# NEW_MINI.net
KiCad netlist of a schematic drawn in Altium Designer
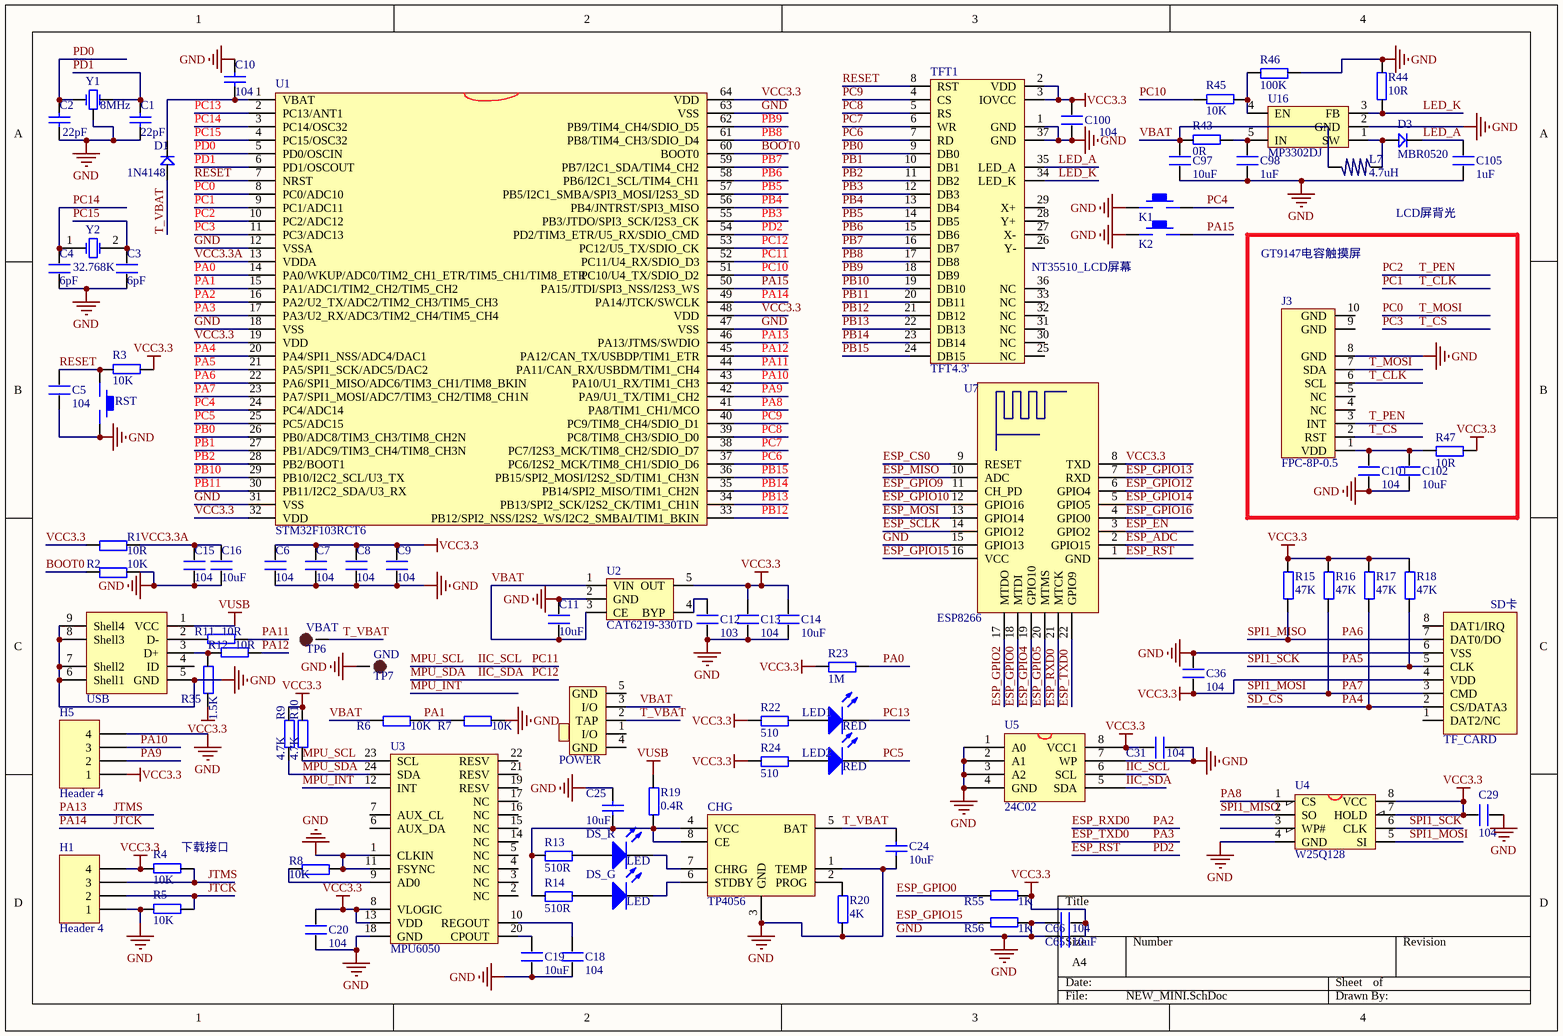
[diagram p0: NEW_MINI.SchDoc]

(export (version "E")
  (design (tool "Eeschema 10.0.6"))
  (components
    (comp (ref "C1") (value "22pF") (footprint "C 0603_M") (libsource (lib "L476") (part "CAP")))
    (comp (ref "C2") (value "22pF") (footprint "C 0603_M") (libsource (lib "L476") (part "CAP")))
    (comp (ref "C3")
      (value "6pF")
      (footprint "C 0603_M")
      (libsource (lib "WarShip V3 STM32103封装库") (part "C"))
    )
    (comp (ref "C4")
      (value "6pF")
      (footprint "C 0603_M")
      (libsource (lib "WarShip V3 STM32103封装库") (part "C"))
    )
    (comp (ref "C5")
      (value "104")
      (footprint "C 0603_M")
      (libsource (lib "WarShip V3 STM32103封装库") (part "C"))
    )
    (comp (ref "C6")
      (value "104")
      (footprint "C 0603_M")
      (libsource (lib "WarShip V3 STM32103封装库") (part "C"))
    )
    (comp (ref "C7")
      (value "104")
      (footprint "C 0603_M")
      (libsource (lib "WarShip V3 STM32103封装库") (part "C"))
    )
    (comp (ref "C8")
      (value "104")
      (footprint "C 0603_M")
      (libsource (lib "WarShip V3 STM32103封装库") (part "C"))
    )
    (comp (ref "C9")
      (value "104")
      (footprint "C 0603_M")
      (libsource (lib "WarShip V3 STM32103封装库") (part "C"))
    )
    (comp (ref "C10") (value "104") (footprint "C 0603_M") (libsource (lib "L476") (part "CAP")))
    (comp (ref "C11")
      (value "10uF")
      (footprint "C 0603_M")
      (libsource (lib "WarShip V3 STM32103封装库") (part "C"))
    )
    (comp (ref "C12")
      (value "103")
      (footprint "C 0603_M")
      (libsource (lib "WarShip V3 STM32103封装库") (part "C"))
    )
    (comp (ref "C13")
      (value "104")
      (footprint "C 0603_M")
      (libsource (lib "WarShip V3 STM32103封装库") (part "C"))
    )
    (comp (ref "C14")
      (value "10uF")
      (footprint "C 0603_M")
      (libsource (lib "WarShip V3 STM32103封装库") (part "C"))
    )
    (comp (ref "C15")
      (value "104")
      (footprint "C 0603_M")
      (libsource (lib "WarShip V3 STM32103封装库") (part "C"))
    )
    (comp (ref "C16")
      (value "10uF")
      (footprint "C 0603_M")
      (libsource (lib "WarShip V3 STM32103封装库") (part "C"))
    )
    (comp (ref "C18")
      (value "104")
      (footprint "C 0603_M")
      (libsource (lib "WarShip V3 STM32103封装库") (part "C"))
    )
    (comp (ref "C19")
      (value "10uF")
      (footprint "C 0603_M")
      (libsource (lib "WarShip V3 STM32103封装库") (part "C"))
    )
    (comp (ref "C20")
      (value "104")
      (footprint "C 0603_M")
      (libsource (lib "WarShip V3 STM32103封装库") (part "C"))
    )
    (comp (ref "C24") (value "10uF") (footprint "C 0603_M") (libsource (lib "L476") (part "CAP")))
    (comp (ref "C25") (value "10uF") (footprint "C 0603_M") (libsource (lib "L476") (part "CAP")))
    (comp (ref "C29")
      (value "104")
      (footprint "C 0603_M")
      (libsource (lib "WarShip V3 STM32103封装库") (part "C"))
    )
    (comp (ref "C31")
      (value "104")
      (footprint "C 0603_M")
      (libsource (lib "WarShip V3 STM32103封装库") (part "C"))
    )
    (comp (ref "C36")
      (value "104")
      (footprint "C 0603_M")
      (libsource (lib "WarShip V3 STM32103封装库") (part "C"))
    )
    (comp (ref "C65") (value "10uF") (footprint "C 0603_M") (libsource (lib "ATK-OV5640摄像头模块封装库") (part "C")))
    (comp (ref "C66") (value "104") (footprint "C 0603_M") (libsource (lib "ATK-OV5640摄像头模块封装库") (part "C")))
    (comp (ref "C97") (value "10uF") (footprint "C 0603_M") (libsource (lib "阿波罗STM32F4&F7底板封装库") (part "C")))
    (comp (ref "C98") (value "1uF") (footprint "C 0603_M") (libsource (lib "阿波罗STM32F4&F7底板封装库") (part "C")))
    (comp (ref "C100") (value "104") (footprint "C 0603_M") (libsource (lib "阿波罗STM32F4&F7底板封装库") (part "C")))
    (comp (ref "C101") (value "104") (footprint "C 0603_M") (libsource (lib "阿波罗STM32F4&F7底板封装库") (part "C")))
    (comp (ref "C102")
      (value "10uF")
      (footprint "C 0603_M")
      (libsource (lib "阿波罗STM32F4&F7底板封装库") (part "C"))
    )
    (comp (ref "C105") (value "1uF") (footprint "C 0603_M") (libsource (lib "阿波罗STM32F4&F7底板封装库") (part "C")))
    (comp (ref "CHG") (value "TP4056") (footprint "SOP8_M") (libsource (lib "tp4056") (part "Component_1")))
    (comp (ref "D1")
      (value "1N4148")
      (footprint "DIODE_SOP")
      (libsource (lib "阿波罗STM32F4&F7底板封装库") (part "D"))
    )
    (comp (ref "D3")
      (value "MBR0520")
      (footprint "SOD-123")
      (description "1N4148")
      (libsource (lib "ATK-4.3' TFTLCD电容触摸屏模块_V1.2") (part "D"))
    )
    (comp (ref "DS_G")
      (value "LED")
      (footprint "LED 0805G")
      (description "Typical RED, GREEN, YELLOW, AMBER GaAs LED")
      (fields (field (name "PUBLISHER") "Altium Limited"))
      (libsource (lib "阿波罗STM32F4&F7底板封装库") (part "LED2"))
    )
    (comp (ref "DS_R")
      (value "LED")
      (footprint "LED 0805R")
      (description "Typical RED, GREEN, YELLOW, AMBER GaAs LED")
      (fields (field (name "PUBLISHER") "Altium Limited"))
      (libsource (lib "阿波罗STM32F4&F7底板封装库") (part "LED2"))
    )
    (comp (ref "GND")
      (value "TP7")
      (footprint "TP-1.5")
      (description "测试点")
      (libsource (lib "STM32F429核心板封装库") (part "TEST-POINT"))
    )
    (comp (ref "H1")
      (value "Header 4")
      (footprint "HDR2.54-LI-4P")
      (description "Header, 4-Pin")
      (fields (field (name "PUBLISHER") "Altium Limited"))
      (libsource (lib "WarShip V3 STM32103封装库") (part "Header 4"))
    )
    (comp (ref "H5")
      (value "Header 4")
      (footprint "HDR2.54-LI-4P")
      (description "Header, 4-Pin")
      (fields (field (name "PUBLISHER") "Altium Limited"))
      (libsource (lib "WarShip V3 STM32103封装库") (part "Header 4"))
    )
    (comp (ref "J3")
      (value "FPC-8P-0.5")
      (footprint "FPC-8P")
      (description "FPC-8P-0.5mm")
      (libsource (lib "ATK-4.3' TFTLCD电容触摸屏模块_V1.2") (part "FPC-8"))
    )
    (comp (ref "K1")
      (value "S-KEY-SMD-324225")
      (footprint "KEY-SOP324225")
      (description "KEY,SMD,324225")
      (libsource (lib "Pandora_STM32L4_Board_V2.4") (part "S-KEY-SMD-324225"))
    )
    (comp (ref "K2")
      (value "S-KEY-SMD-324225")
      (footprint "KEY-SOP324225")
      (description "KEY,SMD,324225")
      (libsource (lib "Pandora_STM32L4_Board_V2.4") (part "S-KEY-SMD-324225"))
    )
    (comp (ref "L7")
      (value "4.7uH")
      (footprint "L_SOP4")
      (libsource (lib "ATK-4.3' TFTLCD电容触摸屏模块_V1.2") (part "L"))
    )
    (comp (ref "LED1")
      (value "RED")
      (footprint "LED 0805R")
      (description "Typical RED, GREEN, YELLOW, AMBER GaAs LED")
      (fields (field (name "PUBLISHER") "Altium Limited"))
      (libsource (lib "阿波罗STM32F4&F7底板封装库") (part "LED2"))
    )
    (comp (ref "LED2")
      (value "RED")
      (footprint "LED 0805R")
      (description "Typical RED, GREEN, YELLOW, AMBER GaAs LED")
      (fields (field (name "PUBLISHER") "Altium Limited"))
      (libsource (lib "阿波罗STM32F4&F7底板封装库") (part "LED2"))
    )
    (comp (ref "POWER")
      (value "BUTTON_DIP3")
      (footprint "MSK-12C01-07")
      (description "拨动开关SS-12F44")
      (libsource (lib "Pandora_STM32L4_Board_V2.4") (part "BUTTON_DIP3"))
    )
    (comp (ref "R1")
      (value "10R")
      (footprint "R 0603_M")
      (libsource (lib "WarShip V3 STM32103封装库") (part "R"))
    )
    (comp (ref "R2")
      (value "10K")
      (footprint "R 0603_M")
      (libsource (lib "WarShip V3 STM32103封装库") (part "R"))
    )
    (comp (ref "R3")
      (value "10K")
      (footprint "R 0603_M")
      (libsource (lib "WarShip V3 STM32103封装库") (part "R"))
    )
    (comp (ref "R4")
      (value "10K")
      (footprint "R 0603_M")
      (libsource (lib "WarShip V3 STM32103封装库") (part "R"))
    )
    (comp (ref "R5")
      (value "10K")
      (footprint "R 0603_M")
      (libsource (lib "WarShip V3 STM32103封装库") (part "R"))
    )
    (comp (ref "R6")
      (value "10K")
      (footprint "R 0603_M")
      (libsource (lib "WarShip V3 STM32103封装库") (part "R"))
    )
    (comp (ref "R7")
      (value "10K")
      (footprint "R 0603_M")
      (libsource (lib "WarShip V3 STM32103封装库") (part "R"))
    )
    (comp (ref "R8")
      (value "10K")
      (footprint "R 0603_M")
      (libsource (lib "WarShip V3 STM32103封装库") (part "R"))
    )
    (comp (ref "R9")
      (value "4.7K")
      (footprint "R 0603_M")
      (libsource (lib "WarShip V3 STM32103封装库") (part "R"))
    )
    (comp (ref "R10")
      (value "4.7K")
      (footprint "R 0603_M")
      (libsource (lib "WarShip V3 STM32103封装库") (part "R"))
    )
    (comp (ref "R11")
      (value "10R")
      (footprint "R 0603_M")
      (libsource (lib "WarShip V3 STM32103封装库") (part "R"))
    )
    (comp (ref "R12")
      (value "10R")
      (footprint "R 0603_M")
      (libsource (lib "WarShip V3 STM32103封装库") (part "R"))
    )
    (comp (ref "R13")
      (value "510R")
      (footprint "R 0603_M")
      (libsource (lib "WarShip V3 STM32103封装库") (part "R"))
    )
    (comp (ref "R14")
      (value "510R")
      (footprint "R 0603_M")
      (libsource (lib "WarShip V3 STM32103封装库") (part "R"))
    )
    (comp (ref "R15")
      (value "47K")
      (footprint "R 0603_M")
      (libsource (lib "WarShip V3 STM32103封装库") (part "R"))
    )
    (comp (ref "R16")
      (value "47K")
      (footprint "R 0603_M")
      (libsource (lib "WarShip V3 STM32103封装库") (part "R"))
    )
    (comp (ref "R17")
      (value "47K")
      (footprint "R 0603_M")
      (libsource (lib "WarShip V3 STM32103封装库") (part "R"))
    )
    (comp (ref "R18")
      (value "47K")
      (footprint "R 0603_M")
      (libsource (lib "WarShip V3 STM32103封装库") (part "R"))
    )
    (comp (ref "R19")
      (value "0.4R")
      (footprint "R 0603_M")
      (libsource (lib "WarShip V3 STM32103封装库") (part "R"))
    )
    (comp (ref "R20")
      (value "4K")
      (footprint "R 0603_M")
      (libsource (lib "WarShip V3 STM32103封装库") (part "R"))
    )
    (comp (ref "R22")
      (value "510")
      (footprint "R 0603_M")
      (libsource (lib "WarShip V3 STM32103封装库") (part "R"))
    )
    (comp (ref "R23")
      (value "1M")
      (footprint "R 0603_M")
      (libsource (lib "WarShip V3 STM32103封装库") (part "R"))
    )
    (comp (ref "R24")
      (value "510")
      (footprint "R 0603_M")
      (libsource (lib "WarShip V3 STM32103封装库") (part "R"))
    )
    (comp (ref "R35")
      (value "1.5K")
      (footprint "R 0603_M")
      (libsource (lib "WarShip V3 STM32103封装库") (part "R"))
    )
    (comp (ref "R43") (value "0R") (footprint "R 0603_M") (libsource (lib "阿波罗STM32F4&F7底板封装库") (part "R")))
    (comp (ref "R44") (value "10R") (footprint "R 0603_M") (libsource (lib "阿波罗STM32F4&F7底板封装库") (part "R")))
    (comp (ref "R45") (value "10K") (footprint "R 0603_M") (libsource (lib "阿波罗STM32F4&F7底板封装库") (part "R")))
    (comp (ref "R46") (value "100K") (footprint "R 0603_M") (libsource (lib "阿波罗STM32F4&F7底板封装库") (part "R")))
    (comp (ref "R47") (value "10R") (footprint "R 0603_M") (libsource (lib "阿波罗STM32F4&F7底板封装库") (part "R")))
    (comp (ref "R55")
      (value "1K")
      (footprint "R 0603_M")
      (libsource (lib "WarShip V3 STM32103封装库") (part "R"))
    )
    (comp (ref "R56")
      (value "1K")
      (footprint "R 0603_M")
      (libsource (lib "WarShip V3 STM32103封装库") (part "R"))
    )
    (comp (ref "RST")
      (value "S-KEY-SMD-324225")
      (footprint "KEY-SOP324225")
      (description "KEY,SMD,324225")
      (libsource (lib "") (part "S-KEY-SMD-324225_1"))
    )
    (comp (ref "TFT1")
      (value "TFT4.3'")
      (footprint "TFT4.3'")
      (description "4.3寸,电容/电阻触摸,分辨率:480*800")
      (libsource (lib "ATK-4.3' TFTLCD电容触摸屏模块_V1.2") (part "TFT4.3‘"))
    )
    (comp (ref "TF_CARD")
      (value "SD-MICRO-TF")
      (footprint "SD-MICRO-TF")
      (description "SD,MICRO,TF")
      (libsource (lib "Pandora_STM32L4_Board_V2.4") (part "SD-MICRO-TF"))
    )
    (comp (ref "U1")
      (value "STM32F103RCT6")
      (footprint "LQFP_64_M")
      (libsource (lib "MiniSTM32 V3.0封装库") (part "STM32F103RDT6"))
    )
    (comp (ref "U2")
      (value "CAT6219-330TD")
      (footprint "SOT-23-5")
      (description "3.3V 500mA LDO")
      (libsource (lib "STM32H743核心板封装库") (part "CAT6219-330TD"))
    )
    (comp (ref "U3")
      (value "MPU6050")
      (footprint "QFN24")
      (description "9轴运动处理传感器")
      (libsource (lib "ATK-MPU6050六轴传感器模块") (part "MPU6050"))
    )
    (comp (ref "U4")
      (value "W25Q128")
      (footprint "SOIC-8")
      (description "W25X16;SST25VF016;MX25L1605")
      (libsource (lib "WarShip V3 STM32103封装库") (part "W25X16"))
    )
    (comp (ref "U5")
      (value "24C02")
      (footprint "SOP-8")
      (libsource (lib "WarShip V3 STM32103封装库") (part "24C256"))
    )
    (comp (ref "U7") (value "ESP8266") (footprint "ESP_12E") (libsource (lib "ESP8266V1.2") (part "ESP8266")))
    (comp (ref "U16")
      (value "MP3302DJ")
      (footprint "SOT-23-5")
      (description "LCD背光IC")
      (libsource (lib "ATK-4.3' TFTLCD电容触摸屏模块_V1.2") (part "MP3302"))
    )
    (comp (ref "USB")
      (value "J-MICRO-USB-5S")
      (footprint "USB-AB-5S")
      (description "Micro USB 5.9有柱脚长1.25加长针")
      (libsource (lib "Pandora_STM32L4_Board_V2.4") (part "J-MICRO-USB-5S"))
    )
    (comp (ref "VBAT")
      (value "TP6")
      (footprint "TP-1.5")
      (description "测试点")
      (libsource (lib "STM32F429核心板封装库") (part "TEST-POINT"))
    )
    (comp (ref "Y1")
      (value "8MHz")
      (footprint "Y-XTAL-3215-3P")
      (description "XTAL,3215,8MHz")
      (libsource (lib "Pandora_STM32L4_Board_V2.4") (part "Y-3215-8M"))
    )
    (comp (ref "Y2")
      (value "32.768K")
      (footprint "OSC 3215-2P")
      (description "Crystal Oscillator")
      (fields (field (name "PUBLISHER") "Altium Limited"))
      (libsource (lib "WarShip V3 STM32103封装库") (part "XTAL"))
    )
  )
  (nets
    (net (code "1") (name "/BOOT0") (class "Default")
      (node (ref "R2") (pin "1") (pintype "passive"))
      (node (ref "U1") (pin "60") (pinfunction "BOOT0_60") (pintype "passive"))
    )
    (net (code "2") (name "/ESP_ADC") (class "Default")
      (node (ref "U7") (pin "2") (pinfunction "GPIO15_2") (pintype "passive"))
    )
    (net (code "3") (name "/ESP_CS0") (class "Default")
      (node (ref "U7") (pin "9") (pinfunction "RESET_9") (pintype "passive"))
    )
    (net (code "4") (name "/ESP_EN") (class "Default")
      (node (ref "U7") (pin "3") (pinfunction "GPIO2_3") (pintype "passive"))
    )
    (net (code "5") (name "/ESP_GPIO0") (class "Default")
      (node (ref "R55") (pin "2") (pintype "passive"))
      (node (ref "U7") (pin "18") (pinfunction "MTDI_18") (pintype "passive"))
    )
    (net (code "6") (name "/ESP_GPIO2") (class "Default")
      (node (ref "U7") (pin "17") (pinfunction "MTDO_17") (pintype "passive"))
    )
    (net (code "7") (name "/ESP_GPIO4") (class "Default")
      (node (ref "U7") (pin "19") (pinfunction "GPIO10_19") (pintype "passive"))
    )
    (net (code "8") (name "/ESP_GPIO5") (class "Default")
      (node (ref "U7") (pin "20") (pinfunction "MTMS_20") (pintype "passive"))
    )
    (net (code "9") (name "/ESP_GPIO9") (class "Default")
      (node (ref "U7") (pin "11") (pinfunction "CH_PD_11") (pintype "passive"))
    )
    (net (code "10") (name "/ESP_GPIO10") (class "Default")
      (node (ref "U7") (pin "12") (pinfunction "GPIO16_12") (pintype "passive"))
    )
    (net (code "11") (name "/ESP_GPIO12") (class "Default")
      (node (ref "U7") (pin "6") (pinfunction "GPIO4_6") (pintype "passive"))
    )
    (net (code "12") (name "/ESP_GPIO13") (class "Default")
      (node (ref "U7") (pin "7") (pinfunction "RXD_7") (pintype "passive"))
    )
    (net (code "13") (name "/ESP_GPIO14") (class "Default")
      (node (ref "U7") (pin "5") (pinfunction "GPIO5_5") (pintype "passive"))
    )
    (net (code "14") (name "/ESP_GPIO15") (class "Default")
      (node (ref "R56") (pin "2") (pintype "passive"))
      (node (ref "U7") (pin "16") (pinfunction "VCC_16") (pintype "passive"))
    )
    (net (code "15") (name "/ESP_GPIO16") (class "Default")
      (node (ref "U7") (pin "4") (pinfunction "GPIO0_4") (pintype "passive"))
    )
    (net (code "16") (name "/ESP_MISO") (class "Default")
      (node (ref "U7") (pin "10") (pinfunction "ADC_10") (pintype "passive"))
    )
    (net (code "17") (name "/ESP_MOSI") (class "Default")
      (node (ref "U7") (pin "13") (pinfunction "GPIO14_13") (pintype "passive"))
    )
    (net (code "18") (name "/ESP_RST") (class "Default")
      (node (ref "U1") (pin "54") (pinfunction "PD2/TIM3_ETR/U5_RX/SDIO_CMD_54") (pintype "passive"))
      (node (ref "U7") (pin "1") (pinfunction "GND_1") (pintype "open_emitter"))
    )
    (net (code "19") (name "/ESP_RXD0") (class "Default")
      (node (ref "U1") (pin "16") (pinfunction "PA2/U2_TX/ADC2/TIM2_CH3/TIM5_CH3_16") (pintype "passive"))
      (node (ref "U7") (pin "21") (pinfunction "MTCK_21") (pintype "passive"))
    )
    (net (code "20") (name "/ESP_SCLK") (class "Default")
      (node (ref "U7") (pin "14") (pinfunction "GPIO12_14") (pintype "passive"))
    )
    (net (code "21") (name "/ESP_TXD0") (class "Default")
      (node (ref "U1") (pin "17") (pinfunction "PA3/U2_RX/ADC3/TIM2_CH4/TIM5_CH4_17") (pintype "passive"))
      (node (ref "U7") (pin "22") (pinfunction "GPIO9_22") (pintype "passive"))
    )
    (net (code "22") (name "/IIC_SCL") (class "Default")
      (node (ref "R10") (pin "1") (pintype "passive"))
      (node (ref "U1") (pin "52") (pinfunction "PC11/U4_RX/SDIO_D3_52") (pintype "passive"))
      (node (ref "U3") (pin "23") (pinfunction "SCL_23") (pintype "passive"))
      (node (ref "U5") (pin "6") (pinfunction "SCL_6") (pintype "passive"))
    )
    (net (code "23") (name "/IIC_SDA") (class "Default")
      (node (ref "R9") (pin "1") (pintype "passive"))
      (node (ref "U1") (pin "53") (pinfunction "PC12/U5_TX/SDIO_CK_53") (pintype "passive"))
      (node (ref "U3") (pin "24") (pinfunction "SDA_24") (pintype "passive"))
      (node (ref "U5") (pin "5") (pinfunction "SDA_5") (pintype "passive"))
    )
    (net (code "24") (name "/JTCK") (class "Default")
      (node (ref "H1") (pin "2") (pinfunction "2_2") (pintype "passive"))
      (node (ref "R5") (pin "1") (pintype "passive"))
      (node (ref "U1") (pin "49") (pinfunction "PA14/JTCK/SWCLK_49") (pintype "passive"))
    )
    (net (code "25") (name "/JTMS") (class "Default")
      (node (ref "H1") (pin "3") (pinfunction "3_3") (pintype "passive"))
      (node (ref "R4") (pin "1") (pintype "passive"))
      (node (ref "U1") (pin "46") (pinfunction "PA13/JTMS/SWDIO_46") (pintype "passive"))
    )
    (net (code "26") (name "/LED_A") (class "Default")
      (node (ref "C105") (pin "1") (pintype "passive"))
      (node (ref "D3") (pin "2") (pintype "passive"))
      (node (ref "TFT1") (pin "35") (pinfunction "LED_A_35") (pintype "passive"))
    )
    (net (code "27") (name "/LED_K") (class "Default")
      (node (ref "R44") (pin "2") (pintype "passive"))
      (node (ref "TFT1") (pin "34") (pinfunction "LED_K_34") (pintype "passive"))
      (node (ref "U16") (pin "3") (pinfunction "FB_3") (pintype "passive"))
    )
    (net (code "28") (name "/MPU_INT") (class "Default")
      (node (ref "U3") (pin "12") (pinfunction "INT_12") (pintype "passive"))
    )
    (net (code "29") (name "/PA0") (class "Default")
      (node (ref "R23") (pin "2") (pintype "passive"))
      (node (ref "U1") (pin "14") (pinfunction "PA0/WKUP/ADC0/TIM2_CH1_ETR/TIM5_CH1/TIM8_ETR_14") (pintype "passive"))
    )
    (net (code "30") (name "/PA1") (class "Default")
      (node (ref "R6") (pin "2") (pintype "passive"))
      (node (ref "R7") (pin "1") (pintype "passive"))
      (node (ref "U1") (pin "15") (pinfunction "PA1/ADC1/TIM2_CH2/TIM5_CH2_15") (pintype "passive"))
    )
    (net (code "31") (name "/PA4") (class "Default")
      (node (ref "R17") (pin "1") (pintype "passive"))
      (node (ref "TF_CARD") (pin "2") (pinfunction "CS/DATA3_2") (pintype "passive"))
      (node (ref "U1") (pin "20") (pinfunction "PA4/SPI1_NSS/ADC4/DAC1_20") (pintype "passive"))
    )
    (net (code "32") (name "/PA5") (class "Default")
      (node (ref "R18") (pin "1") (pintype "passive"))
      (node (ref "TF_CARD") (pin "5") (pinfunction "CLK_5") (pintype "passive"))
      (node (ref "U1") (pin "21") (pinfunction "PA5/SPI1_SCK/ADC5/DAC2_21") (pintype "passive"))
      (node (ref "U4") (pin "6") (pinfunction "CLK_6") (pintype "passive"))
    )
    (net (code "33") (name "/PA6") (class "Default")
      (node (ref "R15") (pin "1") (pintype "passive"))
      (node (ref "TF_CARD") (pin "7") (pinfunction "DAT0/DO_7") (pintype "passive"))
      (node (ref "U1") (pin "22") (pinfunction "PA6/SPI1_MISO/ADC6/TIM3_CH1/TIM8_BKIN_22") (pintype "passive"))
      (node (ref "U4") (pin "2") (pinfunction "SO_2") (pintype "passive"))
    )
    (net (code "34") (name "/PA7") (class "Default")
      (node (ref "R16") (pin "1") (pintype "passive"))
      (node (ref "TF_CARD") (pin "3") (pinfunction "CMD_3") (pintype "passive"))
      (node (ref "U1") (pin "23") (pinfunction "PA7/SPI1_MOSI/ADC7/TIM3_CH2/TIM8_CH1N_23") (pintype "passive"))
      (node (ref "U4") (pin "5") (pinfunction "SI_5") (pintype "passive"))
    )
    (net (code "35") (name "/PA8") (class "Default")
      (node (ref "U1") (pin "41") (pinfunction "PA8/TIM1_CH1/MCO_41") (pintype "passive"))
      (node (ref "U4") (pin "1") (pinfunction "CS_1") (pintype "passive"))
    )
    (net (code "36") (name "/PA9") (class "Default")
      (node (ref "H5") (pin "2") (pinfunction "2_2") (pintype "passive"))
      (node (ref "U1") (pin "42") (pinfunction "PA9/U1_TX/TIM1_CH2_42") (pintype "passive"))
    )
    (net (code "37") (name "/PA10") (class "Default")
      (node (ref "H5") (pin "3") (pinfunction "3_3") (pintype "passive"))
      (node (ref "U1") (pin "43") (pinfunction "PA10/U1_RX/TIM1_CH3_43") (pintype "passive"))
    )
    (net (code "38") (name "/PA11") (class "Default")
      (node (ref "R11") (pin "1") (pintype "passive"))
      (node (ref "U1") (pin "44") (pinfunction "PA11/CAN_RX/USBDM/TIM1_CH4_44") (pintype "passive"))
    )
    (net (code "39") (name "/PA12") (class "Default")
      (node (ref "R12") (pin "1") (pintype "passive"))
      (node (ref "U1") (pin "45") (pinfunction "PA12/CAN_TX/USBDP/TIM1_ETR_45") (pintype "passive"))
    )
    (net (code "40") (name "/PA15") (class "Default")
      (node (ref "K2") (pin "2") (pinfunction "2_2") (pintype "passive"))
      (node (ref "U1") (pin "50") (pinfunction "PA15/JTDI/SPI3_NSS/I2S3_WS_50") (pintype "passive"))
    )
    (net (code "41") (name "/PB0") (class "Default")
      (node (ref "TFT1") (pin "9") (pinfunction "DB0_9") (pintype "passive"))
      (node (ref "U1") (pin "26") (pinfunction "PB0/ADC8/TIM3_CH3/TIM8_CH2N_26") (pintype "passive"))
    )
    (net (code "42") (name "/PB1") (class "Default")
      (node (ref "TFT1") (pin "10") (pinfunction "DB1_10") (pintype "passive"))
      (node (ref "U1") (pin "27") (pinfunction "PB1/ADC9/TIM3_CH4/TIM8_CH3N_27") (pintype "passive"))
    )
    (net (code "43") (name "/PB2") (class "Default")
      (node (ref "TFT1") (pin "11") (pinfunction "DB2_11") (pintype "passive"))
      (node (ref "U1") (pin "28") (pinfunction "PB2/BOOT1_28") (pintype "passive"))
    )
    (net (code "44") (name "/PB3") (class "Default")
      (node (ref "TFT1") (pin "12") (pinfunction "DB3_12") (pintype "passive"))
      (node (ref "U1") (pin "55") (pinfunction "PB3/JTDO/SPI3_SCK/I2S3_CK_55") (pintype "passive"))
    )
    (net (code "45") (name "/PB4") (class "Default")
      (node (ref "TFT1") (pin "13") (pinfunction "DB4_13") (pintype "passive"))
      (node (ref "U1") (pin "56") (pinfunction "PB4/JNTRST/SPI3_MISO_56") (pintype "passive"))
    )
    (net (code "46") (name "/PB5") (class "Default")
      (node (ref "TFT1") (pin "14") (pinfunction "DB5_14") (pintype "passive"))
      (node (ref "U1") (pin "57") (pinfunction "PB5/I2C1_SMBA/SPI3_MOSI/I2S3_SD_57") (pintype "passive"))
    )
    (net (code "47") (name "/PB6") (class "Default")
      (node (ref "TFT1") (pin "15") (pinfunction "DB6_15") (pintype "passive"))
      (node (ref "U1") (pin "58") (pinfunction "PB6/I2C1_SCL/TIM4_CH1_58") (pintype "passive"))
    )
    (net (code "48") (name "/PB7") (class "Default")
      (node (ref "TFT1") (pin "16") (pinfunction "DB7_16") (pintype "passive"))
      (node (ref "U1") (pin "59") (pinfunction "PB7/I2C1_SDA/TIM4_CH2_59") (pintype "passive"))
    )
    (net (code "49") (name "/PB8") (class "Default")
      (node (ref "TFT1") (pin "17") (pinfunction "DB8_17") (pintype "passive"))
      (node (ref "U1") (pin "61") (pinfunction "PB8/TIM4_CH3/SDIO_D4_61") (pintype "passive"))
    )
    (net (code "50") (name "/PB9") (class "Default")
      (node (ref "TFT1") (pin "18") (pinfunction "DB9_18") (pintype "passive"))
      (node (ref "U1") (pin "62") (pinfunction "PB9/TIM4_CH4/SDIO_D5_62") (pintype "passive"))
    )
    (net (code "51") (name "/PB10") (class "Default")
      (node (ref "TFT1") (pin "19") (pinfunction "DB10_19") (pintype "passive"))
      (node (ref "U1") (pin "29") (pinfunction "PB10/I2C2_SCL/U3_TX_29") (pintype "passive"))
    )
    (net (code "52") (name "/PB11") (class "Default")
      (node (ref "TFT1") (pin "20") (pinfunction "DB11_20") (pintype "passive"))
      (node (ref "U1") (pin "30") (pinfunction "PB11/I2C2_SDA/U3_RX_30") (pintype "passive"))
    )
    (net (code "53") (name "/PB12") (class "Default")
      (node (ref "TFT1") (pin "21") (pinfunction "DB12_21") (pintype "passive"))
      (node (ref "U1") (pin "33") (pinfunction "PB12/SPI2_NSS/I2S2_WS/I2C2_SMBAI/TIM1_BKIN_33") (pintype "passive"))
    )
    (net (code "54") (name "/PB13") (class "Default")
      (node (ref "TFT1") (pin "22") (pinfunction "DB13_22") (pintype "passive"))
      (node (ref "U1") (pin "34") (pinfunction "PB13/SPI2_SCK/I2S2_CK/TIM1_CH1N_34") (pintype "passive"))
    )
    (net (code "55") (name "/PB14") (class "Default")
      (node (ref "TFT1") (pin "23") (pinfunction "DB14_23") (pintype "passive"))
      (node (ref "U1") (pin "35") (pinfunction "PB14/SPI2_MISO/TIM1_CH2N_35") (pintype "passive"))
    )
    (net (code "56") (name "/PB15") (class "Default")
      (node (ref "TFT1") (pin "24") (pinfunction "DB15_24") (pintype "passive"))
      (node (ref "U1") (pin "36") (pinfunction "PB15/SPI2_MOSI/I2S2_SD/TIM1_CH3N_36") (pintype "passive"))
    )
    (net (code "57") (name "/PC0") (class "Default")
      (node (ref "J3") (pin "7") (pinfunction "SDA_7") (pintype "passive"))
      (node (ref "U1") (pin "8") (pinfunction "PC0/ADC10_8") (pintype "passive"))
    )
    (net (code "58") (name "/PC1") (class "Default")
      (node (ref "J3") (pin "6") (pinfunction "SCL_6") (pintype "passive"))
      (node (ref "U1") (pin "9") (pinfunction "PC1/ADC11_9") (pintype "passive"))
    )
    (net (code "59") (name "/PC2") (class "Default")
      (node (ref "J3") (pin "3") (pinfunction "INT_3") (pintype "passive"))
      (node (ref "U1") (pin "10") (pinfunction "PC2/ADC12_10") (pintype "passive"))
    )
    (net (code "60") (name "/PC3") (class "Default")
      (node (ref "J3") (pin "2") (pinfunction "RST_2") (pintype "passive"))
      (node (ref "U1") (pin "11") (pinfunction "PC3/ADC13_11") (pintype "passive"))
    )
    (net (code "61") (name "/PC4") (class "Default")
      (node (ref "K1") (pin "2") (pinfunction "2_2") (pintype "passive"))
      (node (ref "U1") (pin "24") (pinfunction "PC4/ADC14_24") (pintype "passive"))
    )
    (net (code "62") (name "/PC5") (class "Default")
      (node (ref "LED2") (pin "2") (pinfunction "K_2") (pintype "passive"))
      (node (ref "U1") (pin "25") (pinfunction "PC5/ADC15_25") (pintype "passive"))
    )
    (net (code "63") (name "/PC6") (class "Default")
      (node (ref "TFT1") (pin "7") (pinfunction "RD_7") (pintype "passive"))
      (node (ref "U1") (pin "37") (pinfunction "PC6/I2S2_MCK/TIM8_CH1/SDIO_D6_37") (pintype "passive"))
    )
    (net (code "64") (name "/PC7") (class "Default")
      (node (ref "TFT1") (pin "6") (pinfunction "WR_6") (pintype "passive"))
      (node (ref "U1") (pin "38") (pinfunction "PC7/I2S3_MCK/TIM8_CH2/SDIO_D7_38") (pintype "passive"))
    )
    (net (code "65") (name "/PC8") (class "Default")
      (node (ref "TFT1") (pin "5") (pinfunction "RS_5") (pintype "passive"))
      (node (ref "U1") (pin "39") (pinfunction "PC8/TIM8_CH3/SDIO_D0_39") (pintype "passive"))
    )
    (net (code "66") (name "/PC9") (class "Default")
      (node (ref "TFT1") (pin "4") (pinfunction "CS_4") (pintype "passive"))
      (node (ref "U1") (pin "40") (pinfunction "PC9/TIM8_CH4/SDIO_D1_40") (pintype "passive"))
    )
    (net (code "67") (name "/PC10") (class "Default")
      (node (ref "R45") (pin "2") (pintype "passive"))
      (node (ref "U1") (pin "51") (pinfunction "PC10/U4_TX/SDIO_D2_51") (pintype "passive"))
    )
    (net (code "68") (name "/PC13") (class "Default")
      (node (ref "LED1") (pin "2") (pinfunction "K_2") (pintype "passive"))
      (node (ref "U1") (pin "2") (pinfunction "PC13/ANT1_2") (pintype "passive"))
    )
    (net (code "69") (name "/PC14") (class "Default")
      (node (ref "C4") (pin "2") (pintype "passive"))
      (node (ref "U1") (pin "3") (pinfunction "PC14/OSC32_3") (pintype "passive"))
      (node (ref "Y2") (pin "1") (pinfunction "OSC1_1") (pintype "passive"))
    )
    (net (code "70") (name "/PC15") (class "Default")
      (node (ref "C3") (pin "2") (pintype "passive"))
      (node (ref "U1") (pin "4") (pinfunction "PC15/OSC32_4") (pintype "passive"))
      (node (ref "Y2") (pin "2") (pinfunction "OSC2_2") (pintype "passive"))
    )
    (net (code "71") (name "/PD0") (class "Default")
      (node (ref "C2") (pin "2") (pinfunction "2_2") (pintype "passive"))
      (node (ref "U1") (pin "5") (pinfunction "PD0/OSCIN_5") (pintype "passive"))
      (node (ref "Y1") (pin "1") (pinfunction "OSC1_1") (pintype "passive"))
    )
    (net (code "72") (name "/PD1") (class "Default")
      (node (ref "C1") (pin "2") (pinfunction "2_2") (pintype "passive"))
      (node (ref "U1") (pin "6") (pinfunction "PD1/OSCOUT_6") (pintype "passive"))
      (node (ref "Y1") (pin "3") (pinfunction "OSC2_3") (pintype "passive"))
    )
    (net (code "73") (name "/RESET") (class "Default")
      (node (ref "C5") (pin "2") (pintype "passive"))
      (node (ref "R3") (pin "2") (pintype "passive"))
      (node (ref "RST") (pin "1") (pinfunction "1_1") (pintype "passive"))
      (node (ref "TFT1") (pin "8") (pinfunction "RST_8") (pintype "passive"))
      (node (ref "U1") (pin "7") (pinfunction "NRST_7") (pintype "passive"))
    )
    (net (code "74") (name "/T_VBAT") (class "Default")
      (node (ref "C24") (pin "1") (pinfunction "1_1") (pintype "passive"))
      (node (ref "CHG") (pin "5") (pinfunction "BAT_5") (pintype "passive"))
      (node (ref "D1") (pin "1") (pintype "passive"))
      (node (ref "POWER") (pin "2") (pinfunction "TAP_2") (pintype "passive"))
      (node (ref "VBAT") (pin "1") (pinfunction "1_1") (pintype "passive"))
    )
    (net (code "75") (name "/VBAT") (class "Default")
      (node (ref "C11") (pin "1") (pintype "passive"))
      (node (ref "C97") (pin "2") (pintype "passive"))
      (node (ref "L7") (pin "2") (pintype "passive"))
      (node (ref "POWER") (pin "3") (pinfunction "I/O_3") (pintype "passive"))
      (node (ref "R43") (pin "2") (pintype "passive"))
      (node (ref "R6") (pin "1") (pintype "passive"))
      (node (ref "U2") (pin "1") (pinfunction "VIN_1") (pintype "passive"))
      (node (ref "U2") (pin "3") (pinfunction "CE_3") (pintype "passive"))
    )
    (net (code "76") (name "/VCC3.3A") (class "Default")
      (node (ref "C15") (pin "2") (pintype "passive"))
      (node (ref "C16") (pin "2") (pintype "passive"))
      (node (ref "R1") (pin "2") (pintype "passive"))
      (node (ref "U1") (pin "13") (pinfunction "VDDA_13") (pintype "passive"))
    )
    (net (code "77") (name "GND") (class "Default")
      (node (ref "C1") (pin "1") (pinfunction "1_1") (pintype "passive"))
      (node (ref "C10") (pin "1") (pinfunction "1_1") (pintype "passive"))
      (node (ref "C100") (pin "1") (pintype "passive"))
      (node (ref "C101") (pin "1") (pintype "passive"))
      (node (ref "C102") (pin "1") (pintype "passive"))
      (node (ref "C105") (pin "2") (pintype "passive"))
      (node (ref "C11") (pin "2") (pintype "passive"))
      (node (ref "C12") (pin "1") (pintype "passive"))
      (node (ref "C13") (pin "1") (pintype "passive"))
      (node (ref "C14") (pin "1") (pintype "passive"))
      (node (ref "C15") (pin "1") (pintype "passive"))
      (node (ref "C16") (pin "1") (pintype "passive"))
      (node (ref "C18") (pin "1") (pintype "passive"))
      (node (ref "C19") (pin "1") (pintype "passive"))
      (node (ref "C2") (pin "1") (pinfunction "1_1") (pintype "passive"))
      (node (ref "C20") (pin "1") (pintype "passive"))
      (node (ref "C24") (pin "2") (pinfunction "2_2") (pintype "passive"))
      (node (ref "C25") (pin "2") (pinfunction "2_2") (pintype "passive"))
      (node (ref "C29") (pin "2") (pintype "passive"))
      (node (ref "C3") (pin "1") (pintype "passive"))
      (node (ref "C31") (pin "2") (pintype "passive"))
      (node (ref "C36") (pin "2") (pintype "passive"))
      (node (ref "C4") (pin "1") (pintype "passive"))
      (node (ref "C5") (pin "1") (pintype "passive"))
      (node (ref "C6") (pin "1") (pintype "passive"))
      (node (ref "C65") (pin "1") (pintype "passive"))
      (node (ref "C66") (pin "1") (pintype "passive"))
      (node (ref "C7") (pin "1") (pintype "passive"))
      (node (ref "C8") (pin "1") (pintype "passive"))
      (node (ref "C9") (pin "1") (pintype "passive"))
      (node (ref "C97") (pin "1") (pintype "passive"))
      (node (ref "C98") (pin "1") (pintype "passive"))
      (node (ref "CHG") (pin "1") (pinfunction "TEMP_1") (pintype "passive"))
      (node (ref "CHG") (pin "3") (pinfunction "GND_3") (pintype "passive"))
      (node (ref "GND") (pin "1") (pinfunction "1_1") (pintype "passive"))
      (node (ref "H1") (pin "1") (pinfunction "1_1") (pintype "passive"))
      (node (ref "H5") (pin "4") (pinfunction "4_4") (pintype "passive"))
      (node (ref "J3") (pin "8") (pinfunction "GND_8") (pintype "passive"))
      (node (ref "K1") (pin "1") (pinfunction "1_1") (pintype "passive"))
      (node (ref "K2") (pin "1") (pinfunction "1_1") (pintype "passive"))
      (node (ref "R2") (pin "2") (pintype "passive"))
      (node (ref "R20") (pin "1") (pintype "passive"))
      (node (ref "R44") (pin "1") (pintype "passive"))
      (node (ref "R46") (pin "2") (pintype "passive"))
      (node (ref "R5") (pin "2") (pintype "passive"))
      (node (ref "R56") (pin "1") (pintype "passive"))
      (node (ref "R7") (pin "2") (pintype "passive"))
      (node (ref "R8") (pin "2") (pintype "passive"))
      (node (ref "RST") (pin "2") (pinfunction "2_2") (pintype "passive"))
      (node (ref "TFT1") (pin "1") (pinfunction "GND_1") (pintype "passive"))
      (node (ref "TFT1") (pin "37") (pinfunction "GND_37") (pintype "passive"))
      (node (ref "TF_CARD") (pin "6") (pinfunction "VSS_6") (pintype "passive"))
      (node (ref "U1") (pin "12") (pinfunction "VSSA_12") (pintype "passive"))
      (node (ref "U1") (pin "18") (pinfunction "VSS_18") (pintype "passive"))
      (node (ref "U1") (pin "31") (pinfunction "VSS_31") (pintype "passive"))
      (node (ref "U1") (pin "47") (pinfunction "VSS_47") (pintype "passive"))
      (node (ref "U1") (pin "63") (pinfunction "VSS_63") (pintype "passive"))
      (node (ref "U16") (pin "2") (pinfunction "GND_2") (pintype "passive"))
      (node (ref "U2") (pin "2") (pinfunction "GND_2") (pintype "passive"))
      (node (ref "U3") (pin "1") (pinfunction "CLKIN_1") (pintype "passive"))
      (node (ref "U3") (pin "11") (pinfunction "FSYNC_11") (pintype "passive"))
      (node (ref "U3") (pin "18") (pinfunction "GND_18") (pintype "passive"))
      (node (ref "U4") (pin "4") (pinfunction "GND_4") (pintype "passive"))
      (node (ref "U5") (pin "1") (pinfunction "A0_1") (pintype "passive"))
      (node (ref "U5") (pin "2") (pinfunction "A1_2") (pintype "passive"))
      (node (ref "U5") (pin "3") (pinfunction "A2_3") (pintype "passive"))
      (node (ref "U5") (pin "4") (pinfunction "GND_4") (pintype "passive"))
      (node (ref "U5") (pin "7") (pinfunction "WP_7") (pintype "passive"))
      (node (ref "U7") (pin "15") (pinfunction "GPIO13_15") (pintype "passive"))
      (node (ref "USB") (pin "5") (pinfunction "GND_5") (pintype "passive"))
      (node (ref "USB") (pin "6") (pinfunction "Shell1_6") (pintype "passive"))
      (node (ref "USB") (pin "7") (pinfunction "Shell2_7") (pintype "passive"))
      (node (ref "USB") (pin "8") (pinfunction "Shell3_8") (pintype "passive"))
      (node (ref "USB") (pin "9") (pinfunction "Shell4_9") (pintype "passive"))
      (node (ref "Y1") (pin "2") (pinfunction "GND_2") (pintype "passive"))
    )
    (net (code "78") (name "Net-(CHG-CE)") (class "Default")
      (node (ref "C25") (pin "1") (pinfunction "1_1") (pintype "passive"))
      (node (ref "CHG") (pin "4") (pinfunction "VCC_4") (pintype "passive"))
      (node (ref "CHG") (pin "8") (pinfunction "CE_8") (pintype "passive"))
      (node (ref "R13") (pin "1") (pintype "passive"))
      (node (ref "R14") (pin "1") (pintype "passive"))
      (node (ref "R19") (pin "1") (pintype "passive"))
    )
    (net (code "79") (name "Net-(CHG-CHRG)") (class "Default")
      (node (ref "CHG") (pin "7") (pinfunction "CHRG_7") (pintype "passive"))
      (node (ref "DS_R") (pin "2") (pinfunction "K_2") (pintype "passive"))
    )
    (net (code "80") (name "Net-(CHG-PROG)") (class "Default")
      (node (ref "CHG") (pin "2") (pinfunction "PROG_2") (pintype "passive"))
      (node (ref "R20") (pin "2") (pintype "passive"))
    )
    (net (code "81") (name "Net-(CHG-STDBY)") (class "Default")
      (node (ref "CHG") (pin "6") (pinfunction "STDBY_6") (pintype "passive"))
      (node (ref "DS_G") (pin "2") (pinfunction "K_2") (pintype "passive"))
    )
    (net (code "82") (name "Net-(DS_G-A)") (class "Default")
      (node (ref "DS_G") (pin "1") (pinfunction "A_1") (pintype "passive"))
      (node (ref "R14") (pin "2") (pintype "passive"))
    )
    (net (code "83") (name "Net-(DS_R-A)") (class "Default")
      (node (ref "DS_R") (pin "1") (pinfunction "A_1") (pintype "passive"))
      (node (ref "R13") (pin "2") (pintype "passive"))
    )
    (net (code "84") (name "Net-(J3-VDD)") (class "Default")
      (node (ref "C101") (pin "2") (pintype "passive"))
      (node (ref "C102") (pin "2") (pintype "passive"))
      (node (ref "J3") (pin "1") (pinfunction "VDD_1") (pintype "passive"))
      (node (ref "R47") (pin "1") (pintype "passive"))
    )
    (net (code "85") (name "Net-(LED1-A)") (class "Default")
      (node (ref "LED1") (pin "1") (pinfunction "A_1") (pintype "passive"))
      (node (ref "R22") (pin "2") (pintype "passive"))
    )
    (net (code "86") (name "Net-(LED2-A)") (class "Default")
      (node (ref "LED2") (pin "1") (pinfunction "A_1") (pintype "passive"))
      (node (ref "R24") (pin "2") (pintype "passive"))
    )
    (net (code "87") (name "Net-(U1-VBAT)") (class "Default")
      (node (ref "C10") (pin "2") (pinfunction "2_2") (pintype "passive"))
      (node (ref "D1") (pin "2") (pintype "passive"))
      (node (ref "U1") (pin "1") (pinfunction "VBAT_1") (pintype "passive"))
    )
    (net (code "88") (name "Net-(U2-BYP)") (class "Default")
      (node (ref "C12") (pin "2") (pintype "passive"))
      (node (ref "U2") (pin "4") (pinfunction "BYP_4") (pintype "passive"))
    )
    (net (code "89") (name "Net-(U3-AD0)") (class "Default")
      (node (ref "R8") (pin "1") (pintype "passive"))
      (node (ref "U3") (pin "9") (pinfunction "AD0_9") (pintype "passive"))
    )
    (net (code "90") (name "Net-(U3-CPOUT)") (class "Default")
      (node (ref "C19") (pin "2") (pintype "passive"))
      (node (ref "U3") (pin "20") (pinfunction "CPOUT_20") (pintype "passive"))
    )
    (net (code "91") (name "Net-(U3-REGOUT)") (class "Default")
      (node (ref "C18") (pin "2") (pintype "passive"))
      (node (ref "U3") (pin "10") (pinfunction "REGOUT_10") (pintype "passive"))
    )
    (net (code "92") (name "Net-(U16-EN)") (class "Default")
      (node (ref "R45") (pin "1") (pintype "passive"))
      (node (ref "R46") (pin "1") (pintype "passive"))
      (node (ref "U16") (pin "4") (pinfunction "EN_4") (pintype "passive"))
    )
    (net (code "93") (name "Net-(U16-IN)") (class "Default")
      (node (ref "C98") (pin "2") (pintype "passive"))
      (node (ref "R43") (pin "1") (pintype "passive"))
      (node (ref "U16") (pin "5") (pinfunction "IN_5") (pintype "passive"))
    )
    (net (code "94") (name "Net-(U16-SW)") (class "Default")
      (node (ref "D3") (pin "1") (pintype "passive"))
      (node (ref "L7") (pin "1") (pintype "passive"))
      (node (ref "U16") (pin "1") (pinfunction "SW_1") (pintype "passive"))
    )
    (net (code "95") (name "Net-(USB-D+)") (class "Default")
      (node (ref "R12") (pin "2") (pintype "passive"))
      (node (ref "R35") (pin "2") (pintype "passive"))
      (node (ref "USB") (pin "3") (pinfunction "D+_3") (pintype "passive"))
    )
    (net (code "96") (name "Net-(USB-D-)") (class "Default")
      (node (ref "R11") (pin "2") (pintype "passive"))
      (node (ref "USB") (pin "2") (pinfunction "D-_2") (pintype "passive"))
    )
    (net (code "97") (name "VCC3.3") (class "Default")
      (node (ref "C100") (pin "2") (pintype "passive"))
      (node (ref "C13") (pin "2") (pintype "passive"))
      (node (ref "C14") (pin "2") (pintype "passive"))
      (node (ref "C20") (pin "2") (pintype "passive"))
      (node (ref "C29") (pin "1") (pintype "passive"))
      (node (ref "C31") (pin "1") (pintype "passive"))
      (node (ref "C36") (pin "1") (pintype "passive"))
      (node (ref "C6") (pin "2") (pintype "passive"))
      (node (ref "C65") (pin "2") (pintype "passive"))
      (node (ref "C66") (pin "2") (pintype "passive"))
      (node (ref "C7") (pin "2") (pintype "passive"))
      (node (ref "C8") (pin "2") (pintype "passive"))
      (node (ref "C9") (pin "2") (pintype "passive"))
      (node (ref "H1") (pin "4") (pinfunction "4_4") (pintype "passive"))
      (node (ref "H5") (pin "1") (pinfunction "1_1") (pintype "passive"))
      (node (ref "R1") (pin "1") (pintype "passive"))
      (node (ref "R10") (pin "2") (pintype "passive"))
      (node (ref "R15") (pin "2") (pintype "passive"))
      (node (ref "R16") (pin "2") (pintype "passive"))
      (node (ref "R17") (pin "2") (pintype "passive"))
      (node (ref "R18") (pin "2") (pintype "passive"))
      (node (ref "R22") (pin "1") (pintype "passive"))
      (node (ref "R23") (pin "1") (pintype "passive"))
      (node (ref "R24") (pin "1") (pintype "passive"))
      (node (ref "R3") (pin "1") (pintype "passive"))
      (node (ref "R35") (pin "1") (pintype "passive"))
      (node (ref "R4") (pin "2") (pintype "passive"))
      (node (ref "R47") (pin "2") (pintype "passive"))
      (node (ref "R55") (pin "1") (pintype "passive"))
      (node (ref "R9") (pin "2") (pintype "passive"))
      (node (ref "TFT1") (pin "2") (pinfunction "VDD_2") (pintype "passive"))
      (node (ref "TFT1") (pin "3") (pinfunction "IOVCC_3") (pintype "passive"))
      (node (ref "TF_CARD") (pin "4") (pinfunction "VDD_4") (pintype "passive"))
      (node (ref "U1") (pin "19") (pinfunction "VDD_19") (pintype "passive"))
      (node (ref "U1") (pin "32") (pinfunction "VDD_32") (pintype "passive"))
      (node (ref "U1") (pin "48") (pinfunction "VDD_48") (pintype "passive"))
      (node (ref "U1") (pin "64") (pinfunction "VDD_64") (pintype "passive"))
      (node (ref "U2") (pin "5") (pinfunction "OUT_5") (pintype "passive"))
      (node (ref "U3") (pin "13") (pinfunction "VDD_13") (pintype "passive"))
      (node (ref "U3") (pin "8") (pinfunction "VLOGIC_8") (pintype "passive"))
      (node (ref "U4") (pin "7") (pinfunction "HOLD_7") (pintype "passive"))
      (node (ref "U4") (pin "8") (pinfunction "VCC_8") (pintype "passive"))
      (node (ref "U5") (pin "8") (pinfunction "VCC1_8") (pintype "passive"))
      (node (ref "U7") (pin "8") (pinfunction "TXD_8") (pintype "passive"))
    )
    (net (code "98") (name "VUSB") (class "Default")
      (node (ref "R19") (pin "2") (pintype "passive"))
      (node (ref "USB") (pin "1") (pinfunction "VCC_1") (pintype "passive"))
    )
    (net (code "99") (name "unconnected-(J3-GND-Pad9)") (class "Default")
      (node (ref "J3") (pin "9") (pinfunction "GND_9") (pintype "passive"))
    )
    (net (code "100") (name "unconnected-(J3-GND-Pad10)") (class "Default")
      (node (ref "J3") (pin "10") (pinfunction "GND_10") (pintype "passive"))
    )
    (net (code "101") (name "unconnected-(J3-NC-Pad4)") (class "Default")
      (node (ref "J3") (pin "4") (pinfunction "NC_4") (pintype "passive"))
    )
    (net (code "102") (name "unconnected-(J3-NC-Pad5)") (class "Default")
      (node (ref "J3") (pin "5") (pinfunction "NC_5") (pintype "passive"))
    )
    (net (code "103") (name "unconnected-(POWER-GND-Pad4)") (class "Default")
      (node (ref "POWER") (pin "4") (pinfunction "GND_4") (pintype "passive"))
    )
    (net (code "104") (name "unconnected-(POWER-GND-Pad5)") (class "Default")
      (node (ref "POWER") (pin "5") (pinfunction "GND_5") (pintype "passive"))
    )
    (net (code "105") (name "unconnected-(POWER-I{slash}O-Pad1)") (class "Default")
      (node (ref "POWER") (pin "1") (pinfunction "I/O_1") (pintype "passive"))
    )
    (net (code "106") (name "unconnected-(TFT1-NC-Pad25)") (class "Default")
      (node (ref "TFT1") (pin "25") (pinfunction "NC_25") (pintype "passive"))
    )
    (net (code "107") (name "unconnected-(TFT1-NC-Pad30)") (class "Default")
      (node (ref "TFT1") (pin "30") (pinfunction "NC_30") (pintype "passive"))
    )
    (net (code "108") (name "unconnected-(TFT1-NC-Pad31)") (class "Default")
      (node (ref "TFT1") (pin "31") (pinfunction "NC_31") (pintype "passive"))
    )
    (net (code "109") (name "unconnected-(TFT1-NC-Pad32)") (class "Default")
      (node (ref "TFT1") (pin "32") (pinfunction "NC_32") (pintype "passive"))
    )
    (net (code "110") (name "unconnected-(TFT1-NC-Pad33)") (class "Default")
      (node (ref "TFT1") (pin "33") (pinfunction "NC_33") (pintype "passive"))
    )
    (net (code "111") (name "unconnected-(TFT1-NC-Pad36)") (class "Default")
      (node (ref "TFT1") (pin "36") (pinfunction "NC_36") (pintype "passive"))
    )
    (net (code "112") (name "unconnected-(TFT1-X+-Pad29)") (class "Default")
      (node (ref "TFT1") (pin "29") (pinfunction "X+_29") (pintype "passive"))
    )
    (net (code "113") (name "unconnected-(TFT1-X--Pad27)") (class "Default")
      (node (ref "TFT1") (pin "27") (pinfunction "X-_27") (pintype "passive"))
    )
    (net (code "114") (name "unconnected-(TFT1-Y+-Pad28)") (class "Default")
      (node (ref "TFT1") (pin "28") (pinfunction "Y+_28") (pintype "passive"))
    )
    (net (code "115") (name "unconnected-(TFT1-Y--Pad26)") (class "Default")
      (node (ref "TFT1") (pin "26") (pinfunction "Y-_26") (pintype "passive"))
    )
    (net (code "116") (name "unconnected-(TF_CARD-DAT1{slash}IRQ-Pad8)") (class "Default")
      (node (ref "TF_CARD") (pin "8") (pinfunction "DAT1/IRQ_8") (pintype "passive"))
    )
    (net (code "117") (name "unconnected-(TF_CARD-DAT2{slash}NC-Pad1)") (class "Default")
      (node (ref "TF_CARD") (pin "1") (pinfunction "DAT2/NC_1") (pintype "passive"))
    )
    (net (code "118") (name "unconnected-(U3-AUX_CL-Pad7)") (class "Default")
      (node (ref "U3") (pin "7") (pinfunction "AUX_CL_7") (pintype "passive"))
    )
    (net (code "119") (name "unconnected-(U3-AUX_DA-Pad6)") (class "Default")
      (node (ref "U3") (pin "6") (pinfunction "AUX_DA_6") (pintype "passive"))
    )
    (net (code "120") (name "unconnected-(U3-NC-Pad2)") (class "Default")
      (node (ref "U3") (pin "2") (pinfunction "NC_2") (pintype "passive"))
    )
    (net (code "121") (name "unconnected-(U3-NC-Pad3)") (class "Default")
      (node (ref "U3") (pin "3") (pinfunction "NC_3") (pintype "passive"))
    )
    (net (code "122") (name "unconnected-(U3-NC-Pad4)") (class "Default")
      (node (ref "U3") (pin "4") (pinfunction "NC_4") (pintype "passive"))
    )
    (net (code "123") (name "unconnected-(U3-NC-Pad5)") (class "Default")
      (node (ref "U3") (pin "5") (pinfunction "NC_5") (pintype "passive"))
    )
    (net (code "124") (name "unconnected-(U3-NC-Pad14)") (class "Default")
      (node (ref "U3") (pin "14") (pinfunction "NC_14") (pintype "passive"))
    )
    (net (code "125") (name "unconnected-(U3-NC-Pad15)") (class "Default")
      (node (ref "U3") (pin "15") (pinfunction "NC_15") (pintype "passive"))
    )
    (net (code "126") (name "unconnected-(U3-NC-Pad16)") (class "Default")
      (node (ref "U3") (pin "16") (pinfunction "NC_16") (pintype "passive"))
    )
    (net (code "127") (name "unconnected-(U3-NC-Pad17)") (class "Default")
      (node (ref "U3") (pin "17") (pinfunction "NC_17") (pintype "passive"))
    )
    (net (code "128") (name "unconnected-(U3-RESV-Pad19)") (class "Default")
      (node (ref "U3") (pin "19") (pinfunction "RESV_19") (pintype "passive"))
    )
    (net (code "129") (name "unconnected-(U3-RESV-Pad21)") (class "Default")
      (node (ref "U3") (pin "21") (pinfunction "RESV_21") (pintype "passive"))
    )
    (net (code "130") (name "unconnected-(U3-RESV-Pad22)") (class "Default")
      (node (ref "U3") (pin "22") (pinfunction "RESV_22") (pintype "passive"))
    )
    (net (code "131") (name "unconnected-(U4-WP#-Pad3)") (class "Default")
      (node (ref "U4") (pin "3") (pinfunction "WP#_3") (pintype "passive"))
    )
    (net (code "132") (name "unconnected-(USB-ID-Pad4)") (class "Default")
      (node (ref "USB") (pin "4") (pinfunction "ID_4") (pintype "passive"))
    )
  )
)
